# ARM_LIMIT_SW.net
KiCad netlist of a schematic drawn in Altium Designer
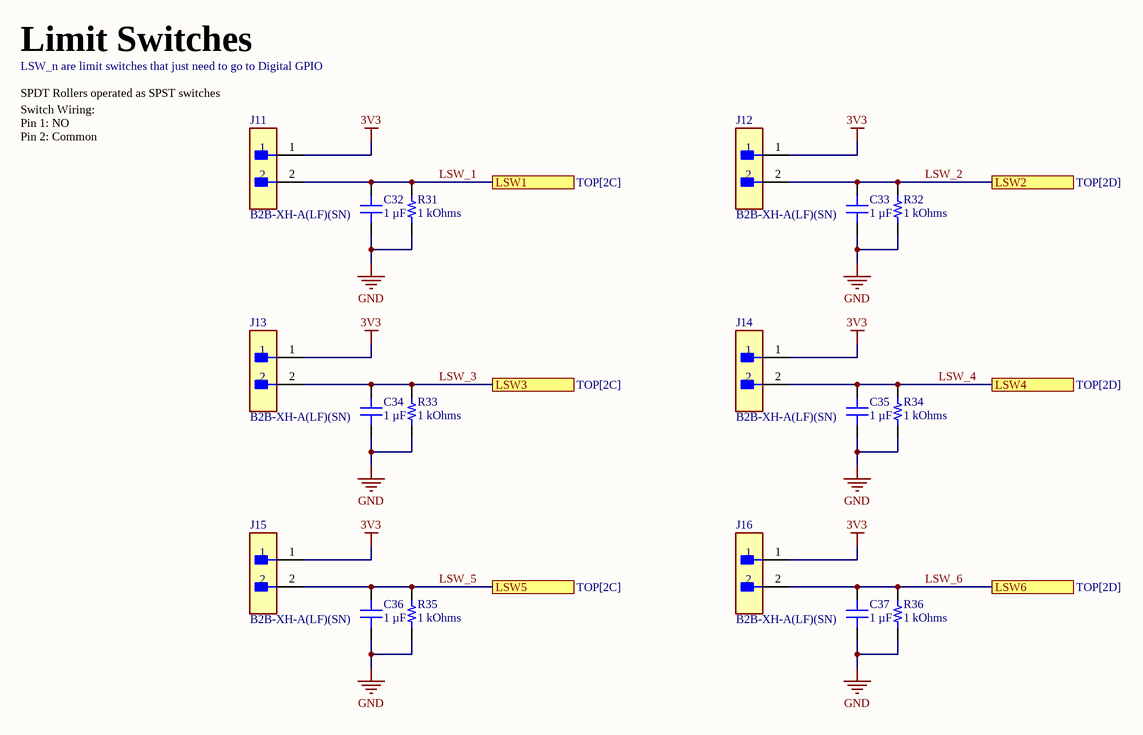
[diagram p0: ARM_LIMIT_SW.SchDoc]

(export (version "E")
  (design (tool "Eeschema 10.0.6"))
  (components
    (comp (ref "C32")
      (value "1 µF")
      (footprint "CAP 0603_1608")
      (description "CAP CER 1UF 10V X7R 0603")
      (fields
        (field (name "PART NUMBER") "MD0603BB105K100NHT-EM")
        (field (name "MANUFACTURER") "Knowles Novacap")
      )
      (libsource (lib "Celestial Altium Library - altium_library") (part "Capacitor"))
    )
    (comp (ref "C33")
      (value "1 µF")
      (footprint "CAP 0603_1608")
      (description "CAP CER 1UF 10V X7R 0603")
      (fields
        (field (name "PART NUMBER") "MD0603BB105K100NHT-EM")
        (field (name "MANUFACTURER") "Knowles Novacap")
      )
      (libsource (lib "Celestial Altium Library - altium_library") (part "Capacitor"))
    )
    (comp (ref "C34")
      (value "1 µF")
      (footprint "CAP 0603_1608")
      (description "CAP CER 1UF 10V X7R 0603")
      (fields
        (field (name "PART NUMBER") "MD0603BB105K100NHT-EM")
        (field (name "MANUFACTURER") "Knowles Novacap")
      )
      (libsource (lib "Celestial Altium Library - altium_library") (part "Capacitor"))
    )
    (comp (ref "C35")
      (value "1 µF")
      (footprint "CAP 0603_1608")
      (description "CAP CER 1UF 10V X7R 0603")
      (fields
        (field (name "PART NUMBER") "MD0603BB105K100NHT-EM")
        (field (name "MANUFACTURER") "Knowles Novacap")
      )
      (libsource (lib "Celestial Altium Library - altium_library") (part "Capacitor"))
    )
    (comp (ref "C36")
      (value "1 µF")
      (footprint "CAP 0603_1608")
      (description "CAP CER 1UF 10V X7R 0603")
      (fields
        (field (name "PART NUMBER") "MD0603BB105K100NHT-EM")
        (field (name "MANUFACTURER") "Knowles Novacap")
      )
      (libsource (lib "Celestial Altium Library - altium_library") (part "Capacitor"))
    )
    (comp (ref "C37")
      (value "1 µF")
      (footprint "CAP 0603_1608")
      (description "CAP CER 1UF 10V X7R 0603")
      (fields
        (field (name "PART NUMBER") "MD0603BB105K100NHT-EM")
        (field (name "MANUFACTURER") "Knowles Novacap")
      )
      (libsource (lib "Celestial Altium Library - altium_library") (part "Capacitor"))
    )
    (comp (ref "J11")
      (value "B2B-XH-A(LF)(SN)")
      (footprint "FP-B2B-XH-A_LF_SN-MFG")
      (description "CONN HEADER VERT 2POS 2.5MM")
      (libsource (lib "Altium Content Vault") (part "3bc925449376181038e59eaffc5286c"))
    )
    (comp (ref "J12")
      (value "B2B-XH-A(LF)(SN)")
      (footprint "FP-B2B-XH-A_LF_SN-MFG")
      (description "CONN HEADER VERT 2POS 2.5MM")
      (libsource (lib "Altium Content Vault") (part "3bc925449376181038e59eaffc5286c"))
    )
    (comp (ref "J13")
      (value "B2B-XH-A(LF)(SN)")
      (footprint "FP-B2B-XH-A_LF_SN-MFG")
      (description "CONN HEADER VERT 2POS 2.5MM")
      (libsource (lib "Altium Content Vault") (part "3bc925449376181038e59eaffc5286c"))
    )
    (comp (ref "J14")
      (value "B2B-XH-A(LF)(SN)")
      (footprint "FP-B2B-XH-A_LF_SN-MFG")
      (description "CONN HEADER VERT 2POS 2.5MM")
      (libsource (lib "Altium Content Vault") (part "3bc925449376181038e59eaffc5286c"))
    )
    (comp (ref "J15")
      (value "B2B-XH-A(LF)(SN)")
      (footprint "FP-B2B-XH-A_LF_SN-MFG")
      (description "CONN HEADER VERT 2POS 2.5MM")
      (libsource (lib "Altium Content Vault") (part "3bc925449376181038e59eaffc5286c"))
    )
    (comp (ref "J16")
      (value "B2B-XH-A(LF)(SN)")
      (footprint "FP-B2B-XH-A_LF_SN-MFG")
      (description "CONN HEADER VERT 2POS 2.5MM")
      (libsource (lib "Altium Content Vault") (part "3bc925449376181038e59eaffc5286c"))
    )
    (comp (ref "R31")
      (value "1 kOhms")
      (footprint "RES 0603_1608")
      (description "1/16 WATTS PRECISION CHIP 1 KILO")
      (fields (field (name "PART NUMBER") "APC0603B1K00N") (field (name "MANUFACTURER") "Ohmite"))
      (libsource (lib "Celestial Altium Library - altium_library") (part "Resistor"))
    )
    (comp (ref "R32")
      (value "1 kOhms")
      (footprint "RES 0603_1608")
      (description "1/16 WATTS PRECISION CHIP 1 KILO")
      (fields (field (name "PART NUMBER") "APC0603B1K00N") (field (name "MANUFACTURER") "Ohmite"))
      (libsource (lib "Celestial Altium Library - altium_library") (part "Resistor"))
    )
    (comp (ref "R33")
      (value "1 kOhms")
      (footprint "RES 0603_1608")
      (description "1/16 WATTS PRECISION CHIP 1 KILO")
      (fields (field (name "PART NUMBER") "APC0603B1K00N") (field (name "MANUFACTURER") "Ohmite"))
      (libsource (lib "Celestial Altium Library - altium_library") (part "Resistor"))
    )
    (comp (ref "R34")
      (value "1 kOhms")
      (footprint "RES 0603_1608")
      (description "1/16 WATTS PRECISION CHIP 1 KILO")
      (fields (field (name "PART NUMBER") "APC0603B1K00N") (field (name "MANUFACTURER") "Ohmite"))
      (libsource (lib "Celestial Altium Library - altium_library") (part "Resistor"))
    )
    (comp (ref "R35")
      (value "1 kOhms")
      (footprint "RES 0603_1608")
      (description "1/16 WATTS PRECISION CHIP 1 KILO")
      (fields (field (name "PART NUMBER") "APC0603B1K00N") (field (name "MANUFACTURER") "Ohmite"))
      (libsource (lib "Celestial Altium Library - altium_library") (part "Resistor"))
    )
    (comp (ref "R36")
      (value "1 kOhms")
      (footprint "RES 0603_1608")
      (description "1/16 WATTS PRECISION CHIP 1 KILO")
      (fields (field (name "PART NUMBER") "APC0603B1K00N") (field (name "MANUFACTURER") "Ohmite"))
      (libsource (lib "Celestial Altium Library - altium_library") (part "Resistor"))
    )
  )
  (nets
    (net (code "1") (name "/LSW_1") (class "Default")
      (node (ref "C32") (pin "2") (pinfunction "2_2") (pintype "passive"))
      (node (ref "J11") (pin "2") (pinfunction "2_2") (pintype "passive"))
      (node (ref "R31") (pin "2") (pinfunction "2_2") (pintype "passive"))
    )
    (net (code "2") (name "/LSW_2") (class "Default")
      (node (ref "C33") (pin "2") (pinfunction "2_2") (pintype "passive"))
      (node (ref "J12") (pin "2") (pinfunction "2_2") (pintype "passive"))
      (node (ref "R32") (pin "2") (pinfunction "2_2") (pintype "passive"))
    )
    (net (code "3") (name "/LSW_3") (class "Default")
      (node (ref "C34") (pin "2") (pinfunction "2_2") (pintype "passive"))
      (node (ref "J13") (pin "2") (pinfunction "2_2") (pintype "passive"))
      (node (ref "R33") (pin "2") (pinfunction "2_2") (pintype "passive"))
    )
    (net (code "4") (name "/LSW_4") (class "Default")
      (node (ref "C35") (pin "2") (pinfunction "2_2") (pintype "passive"))
      (node (ref "J14") (pin "2") (pinfunction "2_2") (pintype "passive"))
      (node (ref "R34") (pin "2") (pinfunction "2_2") (pintype "passive"))
    )
    (net (code "5") (name "/LSW_5") (class "Default")
      (node (ref "C36") (pin "2") (pinfunction "2_2") (pintype "passive"))
      (node (ref "J15") (pin "2") (pinfunction "2_2") (pintype "passive"))
      (node (ref "R35") (pin "2") (pinfunction "2_2") (pintype "passive"))
    )
    (net (code "6") (name "/LSW_6") (class "Default")
      (node (ref "C37") (pin "2") (pinfunction "2_2") (pintype "passive"))
      (node (ref "J16") (pin "2") (pinfunction "2_2") (pintype "passive"))
      (node (ref "R36") (pin "2") (pinfunction "2_2") (pintype "passive"))
    )
    (net (code "7") (name "3V3") (class "Default")
      (node (ref "J11") (pin "1") (pinfunction "1_1") (pintype "passive"))
      (node (ref "J12") (pin "1") (pinfunction "1_1") (pintype "passive"))
      (node (ref "J13") (pin "1") (pinfunction "1_1") (pintype "passive"))
      (node (ref "J14") (pin "1") (pinfunction "1_1") (pintype "passive"))
      (node (ref "J15") (pin "1") (pinfunction "1_1") (pintype "passive"))
      (node (ref "J16") (pin "1") (pinfunction "1_1") (pintype "passive"))
    )
    (net (code "8") (name "GND") (class "Default")
      (node (ref "C32") (pin "1") (pinfunction "1_1") (pintype "passive"))
      (node (ref "C33") (pin "1") (pinfunction "1_1") (pintype "passive"))
      (node (ref "C34") (pin "1") (pinfunction "1_1") (pintype "passive"))
      (node (ref "C35") (pin "1") (pinfunction "1_1") (pintype "passive"))
      (node (ref "C36") (pin "1") (pinfunction "1_1") (pintype "passive"))
      (node (ref "C37") (pin "1") (pinfunction "1_1") (pintype "passive"))
      (node (ref "R31") (pin "1") (pinfunction "1_1") (pintype "passive"))
      (node (ref "R32") (pin "1") (pinfunction "1_1") (pintype "passive"))
      (node (ref "R33") (pin "1") (pinfunction "1_1") (pintype "passive"))
      (node (ref "R34") (pin "1") (pinfunction "1_1") (pintype "passive"))
      (node (ref "R35") (pin "1") (pinfunction "1_1") (pintype "passive"))
      (node (ref "R36") (pin "1") (pinfunction "1_1") (pintype "passive"))
    )
  )
)
